# can_bus_hat.net
KiCad netlist of a schematic drawn in EAGLE
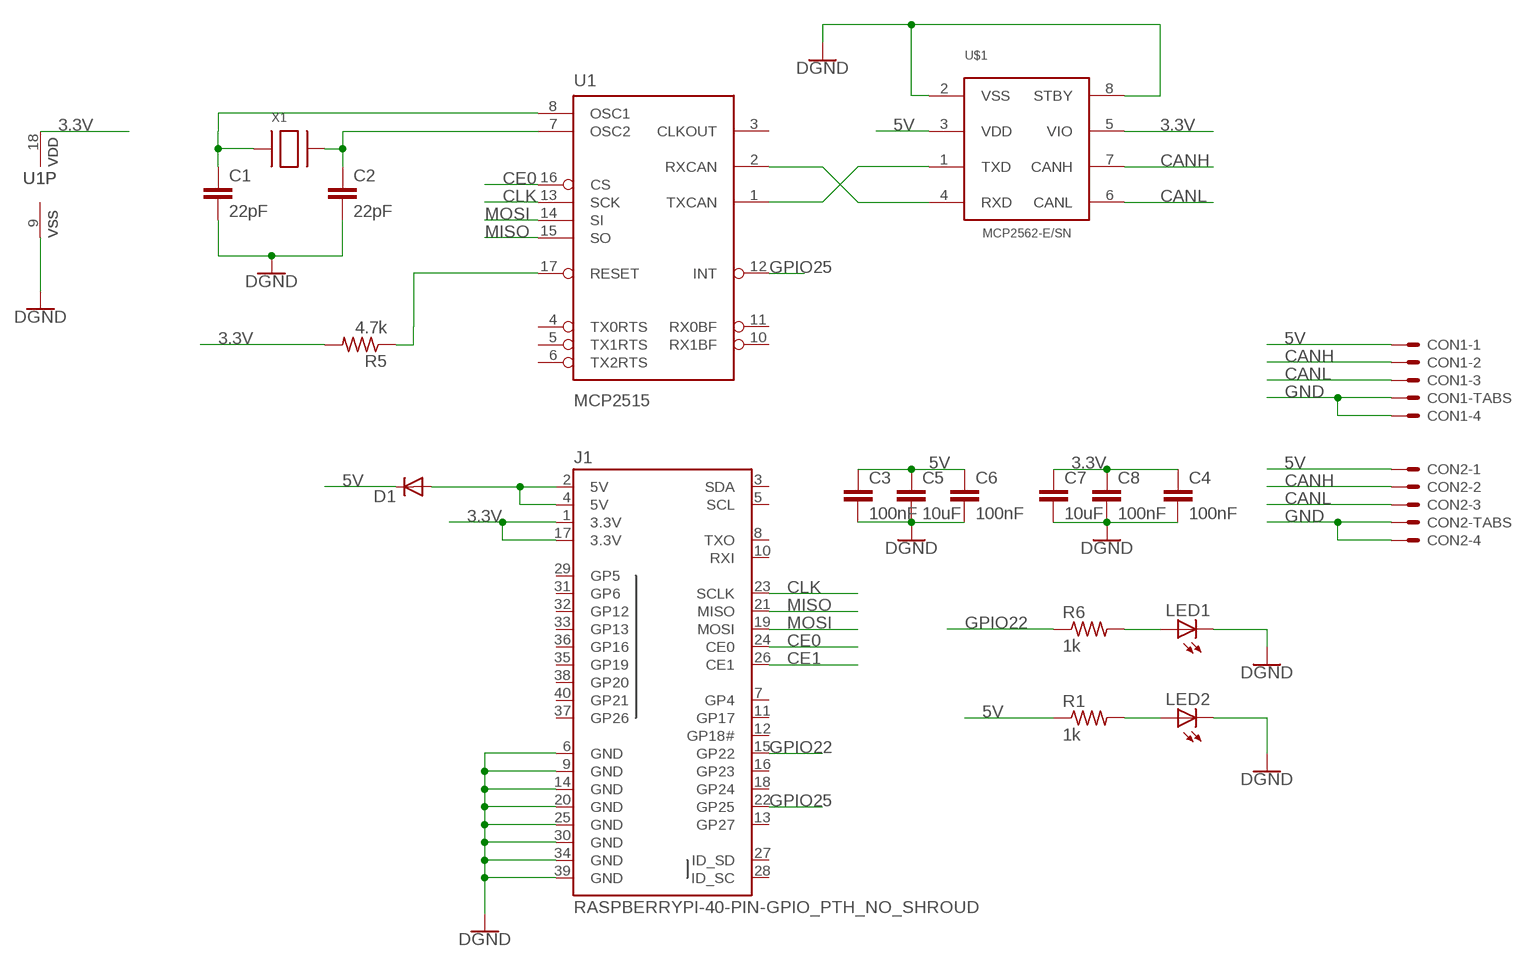
[diagram p0: schematic, sheet 1]

(export (version "E")
  (design (tool "Eeschema 10.0.6"))
  (components
    (comp (ref "C1")
      (value "22pF")
      (footprint "eagle-import:C0805")
      (libsource (lib "eagle-import") (part "C-EUC0805"))
    )
    (comp (ref "C2")
      (value "22pF")
      (footprint "eagle-import:C0805")
      (libsource (lib "eagle-import") (part "C-EUC0805"))
    )
    (comp (ref "C3")
      (value "100nF")
      (footprint "eagle-import:C0805")
      (libsource (lib "eagle-import") (part "C-EUC0805"))
    )
    (comp (ref "C4")
      (value "100nF")
      (footprint "eagle-import:C0805")
      (libsource (lib "eagle-import") (part "C-EUC0805"))
    )
    (comp (ref "C5")
      (value "10uF")
      (footprint "eagle-import:C0805")
      (libsource (lib "eagle-import") (part "C-EUC0805"))
    )
    (comp (ref "C6")
      (value "100nF")
      (footprint "eagle-import:C0805")
      (libsource (lib "eagle-import") (part "C-EUC0805"))
    )
    (comp (ref "C7")
      (value "10uF")
      (footprint "eagle-import:C0805")
      (libsource (lib "eagle-import") (part "C-EUC0805"))
    )
    (comp (ref "C8")
      (value "100nF")
      (footprint "eagle-import:C0805")
      (libsource (lib "eagle-import") (part "C-EUC0805"))
    )
    (comp (ref "CON1")
      (value "SM04B-GHS-TB")
      (footprint "eagle-import:SM04B-GHS-TB")
      (libsource (lib "eagle-import") (part "SM04B-GHS-TB"))
    )
    (comp (ref "CON2")
      (value "SM04B-GHS-TB")
      (footprint "eagle-import:SM04B-GHS-TB")
      (libsource (lib "eagle-import") (part "SM04B-GHS-TB"))
    )
    (comp (ref "D1")
      (value "DIODE-SOD123")
      (footprint "eagle-import:SOD123")
      (libsource (lib "eagle-import") (part "DIODE-SOD123"))
    )
    (comp (ref "J1")
      (value "RASPBERRYPI-40-PIN-GPIO_PTH_NO_SHROUD")
      (footprint "eagle-import:2X20")
      (libsource (lib "eagle-import") (part "RASPBERRYPI-40-PIN-GPIO_PTH_NO_SHROUD"))
    )
    (comp (ref "LED1")
      (value "LEDCHIP-LED0805")
      (footprint "eagle-import:CHIP-LED0805")
      (libsource (lib "eagle-import") (part "LEDCHIP-LED0805"))
    )
    (comp (ref "LED2")
      (value "LEDCHIP-LED0805")
      (footprint "eagle-import:CHIP-LED0805")
      (libsource (lib "eagle-import") (part "LEDCHIP-LED0805"))
    )
    (comp (ref "R1")
      (value "1k")
      (footprint "eagle-import:R0805")
      (libsource (lib "eagle-import") (part "R-US_R0805"))
    )
    (comp (ref "R5")
      (value "4.7k")
      (footprint "eagle-import:R0805")
      (libsource (lib "eagle-import") (part "R-US_R0805"))
    )
    (comp (ref "R6")
      (value "1k")
      (footprint "eagle-import:R0805")
      (libsource (lib "eagle-import") (part "R-US_R0805"))
    )
    (comp (ref "U$1")
      (value "MCP2562-E/SN")
      (footprint "eagle-import:SOIC8")
      (libsource (lib "eagle-import") (part "MCP2562-E/SN"))
    )
    (comp (ref "U1")
      (value "MCP2515")
      (footprint "eagle-import:SO18W")
      (libsource (lib "eagle-import") (part "MCP2515(MCP2510)SO"))
    )
    (comp (ref "X1")
      (value "XTALNX5032")
      (footprint "eagle-import:NX5032")
      (libsource (lib "eagle-import") (part "XTALNX5032"))
    )
  )
  (nets
    (net (code "1") (name "/3.3V") (class "Default")
      (node (ref "C4") (pin "1") (pinfunction "1_1") (pintype "passive"))
      (node (ref "C7") (pin "1") (pinfunction "1_1") (pintype "passive"))
      (node (ref "C8") (pin "1") (pinfunction "1_1") (pintype "passive"))
      (node (ref "J1") (pin "1") (pinfunction "3.3V_1") (pintype "power_in"))
      (node (ref "J1") (pin "17") (pinfunction "3.3V_17") (pintype "power_in"))
      (node (ref "R5") (pin "2") (pinfunction "2_2") (pintype "passive"))
      (node (ref "U$1") (pin "5") (pinfunction "VIO_5") (pintype "bidirectional"))
      (node (ref "U1") (pin "18") (pinfunction "VDD_18") (pintype "power_in"))
    )
    (net (code "2") (name "/5V") (class "Default")
      (node (ref "C3") (pin "1") (pinfunction "1_1") (pintype "passive"))
      (node (ref "C5") (pin "1") (pinfunction "1_1") (pintype "passive"))
      (node (ref "C6") (pin "1") (pinfunction "1_1") (pintype "passive"))
      (node (ref "CON1") (pin "P$1") (pinfunction "S_P$1") (pintype "passive"))
      (node (ref "CON2") (pin "P$1") (pinfunction "S_P$1") (pintype "passive"))
      (node (ref "D1") (pin "C") (pinfunction "C_C") (pintype "passive"))
      (node (ref "R1") (pin "1") (pinfunction "1_1") (pintype "passive"))
      (node (ref "U$1") (pin "3") (pinfunction "VDD_3") (pintype "bidirectional"))
    )
    (net (code "3") (name "/CANH") (class "Default")
      (node (ref "CON1") (pin "P$2") (pinfunction "S_P$2") (pintype "passive"))
      (node (ref "CON2") (pin "P$2") (pinfunction "S_P$2") (pintype "passive"))
      (node (ref "U$1") (pin "7") (pinfunction "CANH_7") (pintype "bidirectional"))
    )
    (net (code "4") (name "/CANL") (class "Default")
      (node (ref "CON1") (pin "P$3") (pinfunction "S_P$3") (pintype "passive"))
      (node (ref "CON2") (pin "P$3") (pinfunction "S_P$3") (pintype "passive"))
      (node (ref "U$1") (pin "6") (pinfunction "CANL_6") (pintype "bidirectional"))
    )
    (net (code "5") (name "/CE0") (class "Default")
      (node (ref "J1") (pin "24") (pinfunction "CE0_24") (pintype "output"))
      (node (ref "U1") (pin "16") (pinfunction "CS_16") (pintype "input"))
    )
    (net (code "6") (name "/CE1") (class "Default")
      (node (ref "J1") (pin "26") (pinfunction "CE1_26") (pintype "output"))
    )
    (net (code "7") (name "/CLK") (class "Default")
      (node (ref "J1") (pin "23") (pinfunction "SCLK_23") (pintype "output"))
      (node (ref "U1") (pin "13") (pinfunction "SCK_13") (pintype "input"))
    )
    (net (code "8") (name "/GPIO22") (class "Default")
      (node (ref "J1") (pin "15") (pinfunction "GP22_15") (pintype "bidirectional"))
      (node (ref "R6") (pin "1") (pinfunction "1_1") (pintype "passive"))
    )
    (net (code "9") (name "/GPIO25") (class "Default")
      (node (ref "J1") (pin "22") (pinfunction "GP25_22") (pintype "bidirectional"))
      (node (ref "U1") (pin "12") (pinfunction "INT_12") (pintype "output"))
    )
    (net (code "10") (name "/MISO") (class "Default")
      (node (ref "J1") (pin "21") (pinfunction "MISO_21") (pintype "input"))
      (node (ref "U1") (pin "15") (pinfunction "SO_15") (pintype "output"))
    )
    (net (code "11") (name "/MOSI") (class "Default")
      (node (ref "J1") (pin "19") (pinfunction "MOSI_19") (pintype "output"))
      (node (ref "U1") (pin "14") (pinfunction "SI_14") (pintype "input"))
    )
    (net (code "12") (name "DGND") (class "Default")
      (node (ref "C1") (pin "2") (pinfunction "2_2") (pintype "passive"))
      (node (ref "C2") (pin "2") (pinfunction "2_2") (pintype "passive"))
      (node (ref "C3") (pin "2") (pinfunction "2_2") (pintype "passive"))
      (node (ref "C4") (pin "2") (pinfunction "2_2") (pintype "passive"))
      (node (ref "C5") (pin "2") (pinfunction "2_2") (pintype "passive"))
      (node (ref "C6") (pin "2") (pinfunction "2_2") (pintype "passive"))
      (node (ref "C7") (pin "2") (pinfunction "2_2") (pintype "passive"))
      (node (ref "C8") (pin "2") (pinfunction "2_2") (pintype "passive"))
      (node (ref "CON1") (pin "P$4") (pinfunction "S_P$4") (pintype "passive"))
      (node (ref "CON1") (pin "P$5") (pinfunction "S_P$5") (pintype "passive"))
      (node (ref "CON1") (pin "P$6") (pinfunction "S_P$6") (pintype "passive"))
      (node (ref "CON2") (pin "P$4") (pinfunction "S_P$4") (pintype "passive"))
      (node (ref "CON2") (pin "P$5") (pinfunction "S_P$5") (pintype "passive"))
      (node (ref "CON2") (pin "P$6") (pinfunction "S_P$6") (pintype "passive"))
      (node (ref "J1") (pin "14") (pinfunction "GND_14") (pintype "power_in"))
      (node (ref "J1") (pin "20") (pinfunction "GND_20") (pintype "power_in"))
      (node (ref "J1") (pin "25") (pinfunction "GND_25") (pintype "power_in"))
      (node (ref "J1") (pin "30") (pinfunction "GND_30") (pintype "power_in"))
      (node (ref "J1") (pin "34") (pinfunction "GND_34") (pintype "power_in"))
      (node (ref "J1") (pin "39") (pinfunction "GND_39") (pintype "power_in"))
      (node (ref "J1") (pin "6") (pinfunction "GND_6") (pintype "power_in"))
      (node (ref "J1") (pin "9") (pinfunction "GND_9") (pintype "power_in"))
      (node (ref "LED1") (pin "C") (pinfunction "C_C") (pintype "passive"))
      (node (ref "LED2") (pin "C") (pinfunction "C_C") (pintype "passive"))
      (node (ref "U$1") (pin "2") (pinfunction "VSS_2") (pintype "bidirectional"))
      (node (ref "U$1") (pin "8") (pinfunction "STBY_8") (pintype "bidirectional"))
      (node (ref "U1") (pin "9") (pinfunction "VSS_9") (pintype "power_in"))
    )
    (net (code "13") (name "Net-(D1-PadA)") (class "Default")
      (node (ref "D1") (pin "A") (pinfunction "A_A") (pintype "passive"))
      (node (ref "J1") (pin "2") (pinfunction "5V_2") (pintype "power_in"))
      (node (ref "J1") (pin "4") (pinfunction "5V_4") (pintype "power_in"))
    )
    (net (code "14") (name "Net-(LED1-PadA)") (class "Default")
      (node (ref "LED1") (pin "A") (pinfunction "A_A") (pintype "passive"))
      (node (ref "R6") (pin "2") (pinfunction "2_2") (pintype "passive"))
    )
    (net (code "15") (name "Net-(LED2-PadA)") (class "Default")
      (node (ref "LED2") (pin "A") (pinfunction "A_A") (pintype "passive"))
      (node (ref "R1") (pin "2") (pinfunction "2_2") (pintype "passive"))
    )
    (net (code "16") (name "Net-(U$1-RXD)") (class "Default")
      (node (ref "U$1") (pin "4") (pinfunction "RXD_4") (pintype "bidirectional"))
      (node (ref "U1") (pin "2") (pinfunction "RXCAN_2") (pintype "input"))
    )
    (net (code "17") (name "Net-(U$1-TXD)") (class "Default")
      (node (ref "U$1") (pin "1") (pinfunction "TXD_1") (pintype "bidirectional"))
      (node (ref "U1") (pin "1") (pinfunction "TXCAN_1") (pintype "output"))
    )
    (net (code "18") (name "Net-(U1A-OSC1)") (class "Default")
      (node (ref "C1") (pin "1") (pinfunction "1_1") (pintype "passive"))
      (node (ref "U1") (pin "8") (pinfunction "OSC1_8") (pintype "input"))
      (node (ref "X1") (pin "P$1") (pinfunction "P$1_P$1") (pintype "bidirectional"))
    )
    (net (code "19") (name "Net-(U1A-OSC2)") (class "Default")
      (node (ref "C2") (pin "1") (pinfunction "1_1") (pintype "passive"))
      (node (ref "U1") (pin "7") (pinfunction "OSC2_7") (pintype "output"))
      (node (ref "X1") (pin "P$2") (pinfunction "P$2_P$2") (pintype "bidirectional"))
    )
    (net (code "20") (name "Net-(U1A-RESET)") (class "Default")
      (node (ref "R5") (pin "1") (pinfunction "1_1") (pintype "passive"))
      (node (ref "U1") (pin "17") (pinfunction "RESET_17") (pintype "input"))
    )
    (net (code "21") (name "unconnected-(J1-GP4-Pad7)") (class "Default")
      (node (ref "J1") (pin "7") (pinfunction "GP4_7") (pintype "bidirectional"))
    )
    (net (code "22") (name "unconnected-(J1-GP5-Pad29)") (class "Default")
      (node (ref "J1") (pin "29") (pinfunction "GP5_29") (pintype "bidirectional"))
    )
    (net (code "23") (name "unconnected-(J1-GP6-Pad31)") (class "Default")
      (node (ref "J1") (pin "31") (pinfunction "GP6_31") (pintype "bidirectional"))
    )
    (net (code "24") (name "unconnected-(J1-GP12-Pad32)") (class "Default")
      (node (ref "J1") (pin "32") (pinfunction "GP12_32") (pintype "bidirectional"))
    )
    (net (code "25") (name "unconnected-(J1-GP13-Pad33)") (class "Default")
      (node (ref "J1") (pin "33") (pinfunction "GP13_33") (pintype "bidirectional"))
    )
    (net (code "26") (name "unconnected-(J1-GP16-Pad36)") (class "Default")
      (node (ref "J1") (pin "36") (pinfunction "GP16_36") (pintype "bidirectional"))
    )
    (net (code "27") (name "unconnected-(J1-GP17-Pad11)") (class "Default")
      (node (ref "J1") (pin "11") (pinfunction "GP17_11") (pintype "bidirectional"))
    )
    (net (code "28") (name "unconnected-(J1-GP18#-Pad12)") (class "Default")
      (node (ref "J1") (pin "12") (pinfunction "GP18#_12") (pintype "bidirectional"))
    )
    (net (code "29") (name "unconnected-(J1-GP19-Pad35)") (class "Default")
      (node (ref "J1") (pin "35") (pinfunction "GP19_35") (pintype "bidirectional"))
    )
    (net (code "30") (name "unconnected-(J1-GP20-Pad38)") (class "Default")
      (node (ref "J1") (pin "38") (pinfunction "GP20_38") (pintype "bidirectional"))
    )
    (net (code "31") (name "unconnected-(J1-GP21-Pad40)") (class "Default")
      (node (ref "J1") (pin "40") (pinfunction "GP21_40") (pintype "bidirectional"))
    )
    (net (code "32") (name "unconnected-(J1-GP23-Pad16)") (class "Default")
      (node (ref "J1") (pin "16") (pinfunction "GP23_16") (pintype "bidirectional"))
    )
    (net (code "33") (name "unconnected-(J1-GP24-Pad18)") (class "Default")
      (node (ref "J1") (pin "18") (pinfunction "GP24_18") (pintype "bidirectional"))
    )
    (net (code "34") (name "unconnected-(J1-GP26-Pad37)") (class "Default")
      (node (ref "J1") (pin "37") (pinfunction "GP26_37") (pintype "bidirectional"))
    )
    (net (code "35") (name "unconnected-(J1-GP27-Pad13)") (class "Default")
      (node (ref "J1") (pin "13") (pinfunction "GP27_13") (pintype "bidirectional"))
    )
    (net (code "36") (name "unconnected-(J1-ID_SC-Pad28)") (class "Default")
      (node (ref "J1") (pin "28") (pinfunction "ID_SC_28") (pintype "bidirectional"))
    )
    (net (code "37") (name "unconnected-(J1-ID_SD-Pad27)") (class "Default")
      (node (ref "J1") (pin "27") (pinfunction "ID_SD_27") (pintype "bidirectional"))
    )
    (net (code "38") (name "unconnected-(J1-RXI-Pad10)") (class "Default")
      (node (ref "J1") (pin "10") (pinfunction "RXI_10") (pintype "input"))
    )
    (net (code "39") (name "unconnected-(J1-SCL-Pad5)") (class "Default")
      (node (ref "J1") (pin "5") (pinfunction "SCL_5") (pintype "bidirectional"))
    )
    (net (code "40") (name "unconnected-(J1-SDA-Pad3)") (class "Default")
      (node (ref "J1") (pin "3") (pinfunction "SDA_3") (pintype "bidirectional"))
    )
    (net (code "41") (name "unconnected-(J1-TXO-Pad8)") (class "Default")
      (node (ref "J1") (pin "8") (pinfunction "TXO_8") (pintype "output"))
    )
    (net (code "42") (name "unconnected-(U1A-CLKOUT-Pad3)") (class "Default")
      (node (ref "U1") (pin "3") (pinfunction "CLKOUT_3") (pintype "output"))
    )
    (net (code "43") (name "unconnected-(U1A-RX0BF-Pad11)") (class "Default")
      (node (ref "U1") (pin "11") (pinfunction "RX0BF_11") (pintype "output"))
    )
    (net (code "44") (name "unconnected-(U1A-RX1BF-Pad10)") (class "Default")
      (node (ref "U1") (pin "10") (pinfunction "RX1BF_10") (pintype "output"))
    )
    (net (code "45") (name "unconnected-(U1A-TX0RTS-Pad4)") (class "Default")
      (node (ref "U1") (pin "4") (pinfunction "TX0RTS_4") (pintype "input"))
    )
    (net (code "46") (name "unconnected-(U1A-TX1RTS-Pad5)") (class "Default")
      (node (ref "U1") (pin "5") (pinfunction "TX1RTS_5") (pintype "input"))
    )
    (net (code "47") (name "unconnected-(U1A-TX2RTS-Pad6)") (class "Default")
      (node (ref "U1") (pin "6") (pinfunction "TX2RTS_6") (pintype "input"))
    )
  )
)
